# single-phase_bridge_test1.net
KiCad netlist of a schematic drawn in Altium Designer
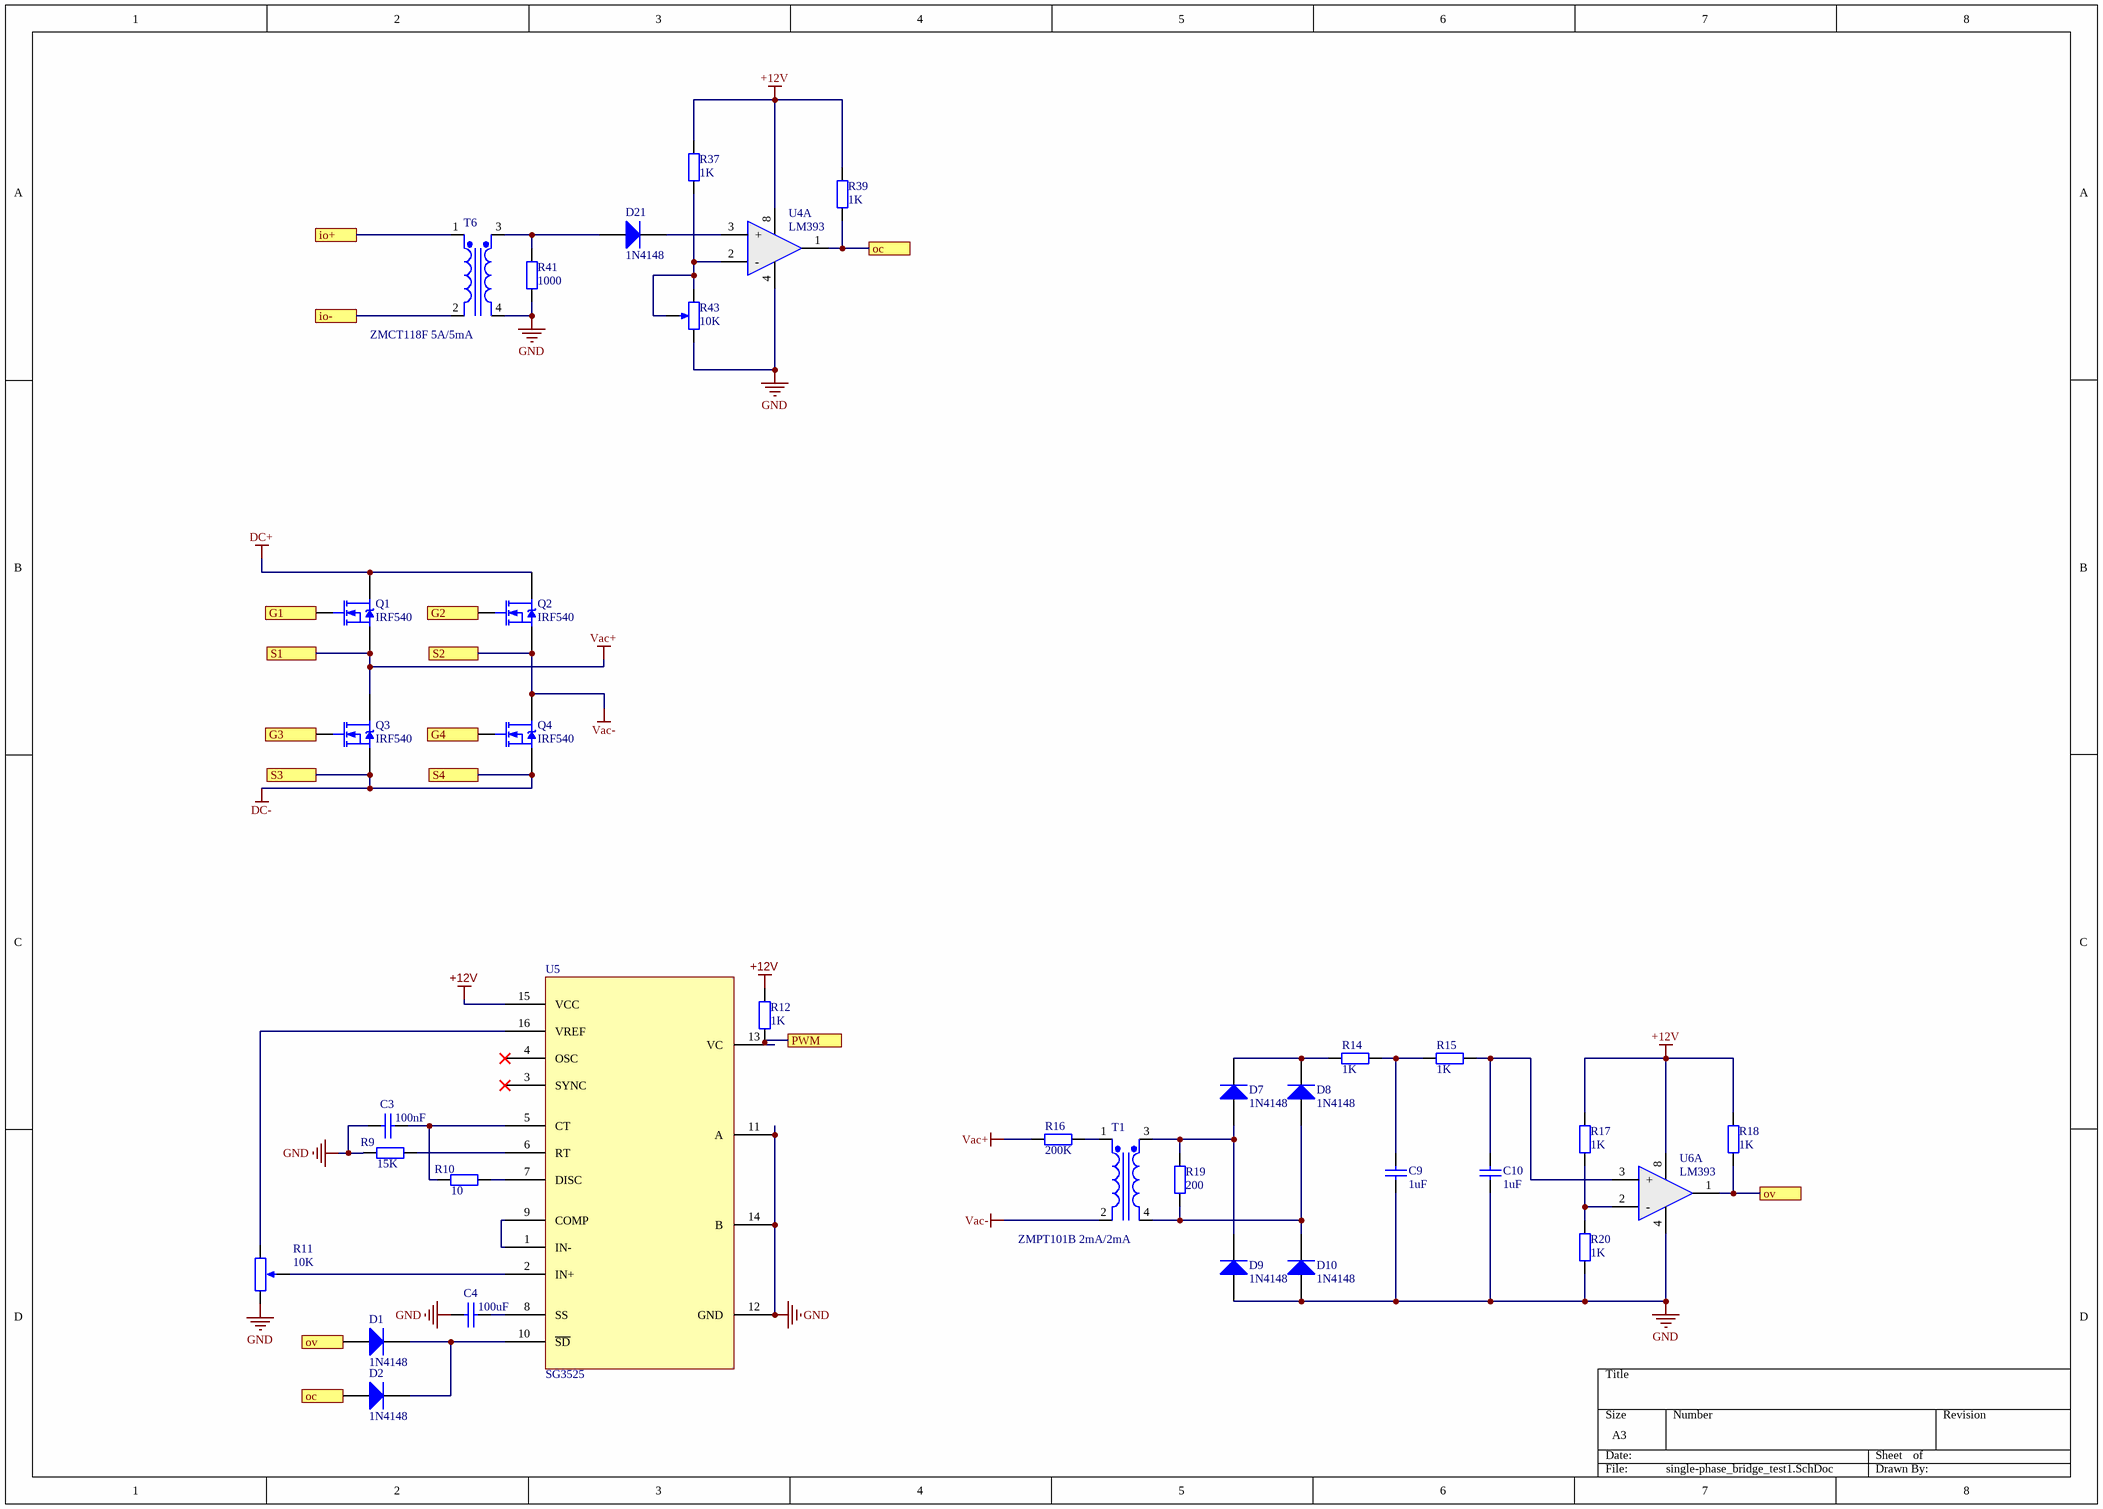
[diagram p0: single-phase_bridge_test1.SchDoc]

(export (version "E")
  (design (tool "Eeschema 10.0.6"))
  (components
    (comp (ref "C3")
      (value "100nF")
      (footprint "C0603")
      (description "Capacitor")
      (libsource (lib "XS") (part "Cap"))
    )
    (comp (ref "C4")
      (value "100uF")
      (footprint "C0603")
      (description "Capacitor")
      (libsource (lib "XS") (part "Cap"))
    )
    (comp (ref "C9")
      (value "1uF")
      (footprint "0805C")
      (description "无极性电容")
      (fields (field (name "Comment") "Cap") (field (name "PUBLISHER") "Altium Limited"))
      (libsource (lib "Capacitors") (part "Cap"))
    )
    (comp (ref "C10")
      (value "1uF")
      (footprint "0805C")
      (description "无极性电容")
      (fields (field (name "Comment") "Cap") (field (name "PUBLISHER") "Altium Limited"))
      (libsource (lib "Capacitors") (part "Cap"))
    )
    (comp (ref "D1")
      (value "Diode")
      (footprint "DIODE-SMA")
      (description "二极管")
      (fields (field (name "TYPE") "1N4148") (field (name "PUBLISHER") "Altium Limited"))
      (libsource (lib "Diodes") (part "Diode"))
    )
    (comp (ref "D2")
      (value "Diode")
      (footprint "DIODE-SMA")
      (description "二极管")
      (fields (field (name "TYPE") "1N4148") (field (name "PUBLISHER") "Altium Limited"))
      (libsource (lib "Diodes") (part "Diode"))
    )
    (comp (ref "D7")
      (value "Diode")
      (footprint "DIODE-SMA")
      (description "二极管")
      (fields (field (name "TYPE") "1N4148") (field (name "PUBLISHER") "Altium Limited"))
      (libsource (lib "Diodes") (part "Diode"))
    )
    (comp (ref "D8")
      (value "Diode")
      (footprint "DIODE-SMA")
      (description "二极管")
      (fields (field (name "TYPE") "1N4148") (field (name "PUBLISHER") "Altium Limited"))
      (libsource (lib "Diodes") (part "Diode"))
    )
    (comp (ref "D9")
      (value "Diode")
      (footprint "DIODE-SMA")
      (description "二极管")
      (fields (field (name "TYPE") "1N4148") (field (name "PUBLISHER") "Altium Limited"))
      (libsource (lib "Diodes") (part "Diode"))
    )
    (comp (ref "D10")
      (value "Diode")
      (footprint "DIODE-SMA")
      (description "二极管")
      (fields (field (name "TYPE") "1N4148") (field (name "PUBLISHER") "Altium Limited"))
      (libsource (lib "Diodes") (part "Diode"))
    )
    (comp (ref "D21")
      (value "Diode")
      (footprint "DIODE-SMA")
      (description "二极管")
      (fields (field (name "TYPE") "1N4148") (field (name "PUBLISHER") "Altium Limited"))
      (libsource (lib "Diodes") (part "Diode"))
    )
    (comp (ref "Q1")
      (value "IRF540")
      (footprint "TO-220")
      (description "N-Channel MOSFET")
      (fields (field (name "PUBLISHER") "Altium Limited"))
      (libsource (lib "Transistors") (part "MOSFET-N"))
    )
    (comp (ref "Q2")
      (value "IRF540")
      (footprint "TO-220")
      (description "N-Channel MOSFET")
      (fields (field (name "PUBLISHER") "Altium Limited"))
      (libsource (lib "Transistors") (part "MOSFET-N"))
    )
    (comp (ref "Q3")
      (value "IRF540")
      (footprint "TO-220")
      (description "N-Channel MOSFET")
      (fields (field (name "PUBLISHER") "Altium Limited"))
      (libsource (lib "Transistors") (part "MOSFET-N"))
    )
    (comp (ref "Q4")
      (value "IRF540")
      (footprint "TO-220")
      (description "N-Channel MOSFET")
      (fields (field (name "PUBLISHER") "Altium Limited"))
      (libsource (lib "Transistors") (part "MOSFET-N"))
    )
    (comp (ref "R9")
      (value "15K")
      (footprint "R0805_3D")
      (description "贴片电阻")
      (fields (field (name "Comment") "Res") (field (name "PUBLISHER") "Altium Limited"))
      (libsource (lib "XS") (part "Res"))
    )
    (comp (ref "R10")
      (value "10")
      (footprint "R0805_3D")
      (description "贴片电阻")
      (fields (field (name "Comment") "Res") (field (name "PUBLISHER") "Altium Limited"))
      (libsource (lib "XS") (part "Res"))
    )
    (comp (ref "R11")
      (value "10K")
      (footprint "RPOT")
      (description "精密可调电阻")
      (fields (field (name "Comment") "RPot") (field (name "PUBLISHER") "Altium Limited"))
      (libsource (lib "XS") (part "RPot"))
    )
    (comp (ref "R12")
      (value "1K")
      (footprint "R0805_3D")
      (description "贴片电阻")
      (fields (field (name "Comment") "Res") (field (name "PUBLISHER") "Altium Limited"))
      (libsource (lib "") (part "Res_1"))
    )
    (comp (ref "R14")
      (value "1K")
      (footprint "0805R")
      (description "Resistor")
      (fields (field (name "Comment") "Res2") (field (name "PUBLISHER") "Altium Limited"))
      (libsource (lib "") (part "Res2_1"))
    )
    (comp (ref "R15")
      (value "1K")
      (footprint "0805R")
      (description "Resistor")
      (fields (field (name "Comment") "Res2") (field (name "PUBLISHER") "Altium Limited"))
      (libsource (lib "") (part "Res2_1"))
    )
    (comp (ref "R16")
      (value "200K")
      (footprint "0805R")
      (description "Resistor")
      (fields (field (name "Comment") "Res2") (field (name "PUBLISHER") "Altium Limited"))
      (libsource (lib "") (part "Res2_2"))
    )
    (comp (ref "R17")
      (value "1K")
      (footprint "0805R")
      (description "电阻")
      (fields (field (name "PUBLISHER") "Altium Limited"))
      (libsource (lib "Resistors") (part "Res"))
    )
    (comp (ref "R18")
      (value "1K")
      (footprint "0805R")
      (description "电阻")
      (fields (field (name "PUBLISHER") "Altium Limited"))
      (libsource (lib "Resistors") (part "Res"))
    )
    (comp (ref "R19")
      (value "200")
      (footprint "0805R")
      (description "Resistor")
      (fields (field (name "Comment") "Res2") (field (name "PUBLISHER") "Altium Limited"))
      (libsource (lib "Miscellaneous Devices") (part "Res2"))
    )
    (comp (ref "R20")
      (value "1K")
      (footprint "0805R")
      (description "电阻")
      (fields (field (name "PUBLISHER") "Altium Limited"))
      (libsource (lib "Resistors") (part "Res"))
    )
    (comp (ref "R37")
      (value "1K")
      (footprint "0805R")
      (description "电阻")
      (fields (field (name "PUBLISHER") "Altium Limited"))
      (libsource (lib "Resistors") (part "Res"))
    )
    (comp (ref "R39")
      (value "1K")
      (footprint "0805R")
      (description "电阻")
      (fields (field (name "PUBLISHER") "Altium Limited"))
      (libsource (lib "Resistors") (part "Res"))
    )
    (comp (ref "R41")
      (value "1000")
      (footprint "0805R")
      (description "Resistor")
      (fields (field (name "Comment") "Res2") (field (name "PUBLISHER") "Altium Limited"))
      (libsource (lib "Miscellaneous Devices") (part "Res2"))
    )
    (comp (ref "R43")
      (value "10K")
      (footprint "RPot_3296W")
      (description "电位器")
      (fields (field (name "PUBLISHER") "Altium Limited"))
      (libsource (lib "Resistors") (part "RPot"))
    )
    (comp (ref "T1")
      (value "ZMPT101B 2mA/2mA")
      (footprint "PT ZMPT101B")
      (libsource (lib "刘爽") (part "DL-PT202H1"))
    )
    (comp (ref "T6")
      (value "ZMCT118F 5A/5mA")
      (footprint "PT ZMPT101B")
      (libsource (lib "刘爽") (part "DL-PT202H1"))
    )
    (comp (ref "U4")
      (value "LM393")
      (footprint "DIP8")
      (description "2比较器芯片")
      (libsource (lib "Amplifier") (part "LM393"))
    )
    (comp (ref "U5") (value "SG3525") (libsource (lib "XS") (part "SG3525")))
    (comp (ref "U6")
      (value "LM393")
      (footprint "DIP8")
      (description "2比较器芯片")
      (libsource (lib "Amplifier") (part "LM393"))
    )
  )
  (nets
    (net (code "1") (name "+12V") (class "Default")
      (node (ref "R12") (pin "2") (pinfunction "2_2") (pintype "passive"))
      (node (ref "R17") (pin "2") (pinfunction "2_2") (pintype "passive"))
      (node (ref "R18") (pin "2") (pinfunction "2_2") (pintype "passive"))
      (node (ref "R37") (pin "2") (pinfunction "2_2") (pintype "passive"))
      (node (ref "R39") (pin "2") (pinfunction "2_2") (pintype "passive"))
      (node (ref "U4") (pin "8") (pinfunction "V-_8") (pintype "passive"))
      (node (ref "U5") (pin "15") (pinfunction "VCC_15") (pintype "passive"))
      (node (ref "U6") (pin "8") (pinfunction "V-_8") (pintype "passive"))
    )
    (net (code "2") (name "/G1") (class "Default")
      (node (ref "Q1") (pin "1") (pinfunction "G_1") (pintype "passive"))
    )
    (net (code "3") (name "/G2") (class "Default")
      (node (ref "Q2") (pin "1") (pinfunction "G_1") (pintype "passive"))
    )
    (net (code "4") (name "/G3") (class "Default")
      (node (ref "Q3") (pin "1") (pinfunction "G_1") (pintype "passive"))
    )
    (net (code "5") (name "/G4") (class "Default")
      (node (ref "Q4") (pin "1") (pinfunction "G_1") (pintype "passive"))
    )
    (net (code "6") (name "/PWM") (class "Default")
      (node (ref "R12") (pin "1") (pinfunction "1_1") (pintype "passive"))
      (node (ref "U5") (pin "13") (pinfunction "VC_13") (pintype "passive"))
    )
    (net (code "7") (name "/io+") (class "Default")
      (node (ref "T6") (pin "1") (pinfunction "Pri+_1") (pintype "passive"))
    )
    (net (code "8") (name "/io-") (class "Default")
      (node (ref "T6") (pin "2") (pinfunction "Pri-_2") (pintype "passive"))
    )
    (net (code "9") (name "/oc") (class "Default")
      (node (ref "D2") (pin "1") (pinfunction "A_1") (pintype "passive"))
      (node (ref "R39") (pin "1") (pinfunction "1_1") (pintype "passive"))
      (node (ref "U4") (pin "1") (pinfunction "OUT_1") (pintype "passive"))
    )
    (net (code "10") (name "/ov") (class "Default")
      (node (ref "D1") (pin "1") (pinfunction "A_1") (pintype "passive"))
      (node (ref "R18") (pin "1") (pinfunction "1_1") (pintype "passive"))
      (node (ref "U6") (pin "1") (pinfunction "OUT_1") (pintype "passive"))
    )
    (net (code "11") (name "DC+") (class "Default")
      (node (ref "Q1") (pin "2") (pinfunction "D_2") (pintype "passive"))
      (node (ref "Q2") (pin "2") (pinfunction "D_2") (pintype "passive"))
    )
    (net (code "12") (name "DC-") (class "Default")
      (node (ref "Q3") (pin "3") (pinfunction "S_3") (pintype "passive"))
      (node (ref "Q4") (pin "3") (pinfunction "S_3") (pintype "passive"))
    )
    (net (code "13") (name "GND") (class "Default")
      (node (ref "C10") (pin "1") (pinfunction "1_1") (pintype "passive"))
      (node (ref "C3") (pin "1") (pinfunction "1_1") (pintype "passive"))
      (node (ref "C4") (pin "1") (pinfunction "1_1") (pintype "passive"))
      (node (ref "C9") (pin "1") (pinfunction "1_1") (pintype "passive"))
      (node (ref "D10") (pin "1") (pinfunction "A_1") (pintype "passive"))
      (node (ref "D9") (pin "1") (pinfunction "A_1") (pintype "passive"))
      (node (ref "R11") (pin "1") (pinfunction "TOP_1") (pintype "passive"))
      (node (ref "R20") (pin "1") (pinfunction "1_1") (pintype "passive"))
      (node (ref "R41") (pin "1") (pinfunction "1_1") (pintype "passive"))
      (node (ref "R43") (pin "1") (pinfunction "TOP_1") (pintype "passive"))
      (node (ref "R9") (pin "1") (pinfunction "1_1") (pintype "passive"))
      (node (ref "T6") (pin "4") (pinfunction "Sec-_4") (pintype "passive"))
      (node (ref "U4") (pin "4") (pinfunction "V+_4") (pintype "passive"))
      (node (ref "U5") (pin "11") (pinfunction "A_11") (pintype "passive"))
      (node (ref "U5") (pin "12") (pinfunction "GND_12") (pintype "passive"))
      (node (ref "U5") (pin "14") (pinfunction "B_14") (pintype "passive"))
      (node (ref "U6") (pin "4") (pinfunction "V+_4") (pintype "passive"))
    )
    (net (code "14") (name "Net-(C9-Pad2)") (class "Default")
      (node (ref "C9") (pin "2") (pinfunction "2_2") (pintype "passive"))
      (node (ref "R14") (pin "1") (pinfunction "1_1") (pintype "passive"))
      (node (ref "R15") (pin "2") (pinfunction "2_2") (pintype "passive"))
    )
    (net (code "15") (name "Net-(D1-K)") (class "Default")
      (node (ref "D1") (pin "2") (pinfunction "K_2") (pintype "passive"))
      (node (ref "D2") (pin "2") (pinfunction "K_2") (pintype "passive"))
      (node (ref "U5") (pin "10") (pinfunction "~{SD}_10") (pintype "passive"))
    )
    (net (code "16") (name "Net-(D7-A)") (class "Default")
      (node (ref "D7") (pin "1") (pinfunction "A_1") (pintype "passive"))
      (node (ref "D9") (pin "2") (pinfunction "K_2") (pintype "passive"))
      (node (ref "R19") (pin "2") (pinfunction "2_2") (pintype "passive"))
      (node (ref "T1") (pin "3") (pinfunction "Sec+_3") (pintype "passive"))
    )
    (net (code "17") (name "Net-(D7-K)") (class "Default")
      (node (ref "D7") (pin "2") (pinfunction "K_2") (pintype "passive"))
      (node (ref "D8") (pin "2") (pinfunction "K_2") (pintype "passive"))
      (node (ref "R14") (pin "2") (pinfunction "2_2") (pintype "passive"))
    )
    (net (code "18") (name "Net-(D10-K)") (class "Default")
      (node (ref "D10") (pin "2") (pinfunction "K_2") (pintype "passive"))
      (node (ref "D8") (pin "1") (pinfunction "A_1") (pintype "passive"))
      (node (ref "R19") (pin "1") (pinfunction "1_1") (pintype "passive"))
      (node (ref "T1") (pin "4") (pinfunction "Sec-_4") (pintype "passive"))
    )
    (net (code "19") (name "Net-(D21-A)") (class "Default")
      (node (ref "D21") (pin "1") (pinfunction "A_1") (pintype "passive"))
      (node (ref "R41") (pin "2") (pinfunction "2_2") (pintype "passive"))
      (node (ref "T6") (pin "3") (pinfunction "Sec+_3") (pintype "passive"))
    )
    (net (code "20") (name "Net-(D21-K)") (class "Default")
      (node (ref "D21") (pin "2") (pinfunction "K_2") (pintype "passive"))
      (node (ref "U4") (pin "3") (pinfunction "+_3") (pintype "passive"))
    )
    (net (code "21") (name "Net-(R11-BOT)") (class "Default")
      (node (ref "R11") (pin "3") (pinfunction "BOT_3") (pintype "passive"))
      (node (ref "U5") (pin "16") (pinfunction "VREF_16") (pintype "passive"))
    )
    (net (code "22") (name "Net-(R11-TAP)") (class "Default")
      (node (ref "R11") (pin "2") (pinfunction "TAP_2") (pintype "passive"))
      (node (ref "U5") (pin "2") (pinfunction "IN+_2") (pintype "passive"))
    )
    (net (code "23") (name "Net-(R43-BOT)") (class "Default")
      (node (ref "R37") (pin "1") (pinfunction "1_1") (pintype "passive"))
      (node (ref "R43") (pin "2") (pinfunction "TAP_2") (pintype "passive"))
      (node (ref "R43") (pin "3") (pinfunction "BOT_3") (pintype "passive"))
      (node (ref "U4") (pin "2") (pinfunction "-_2") (pintype "passive"))
    )
    (net (code "24") (name "Net-(T1-Pri+)") (class "Default")
      (node (ref "R16") (pin "2") (pinfunction "2_2") (pintype "passive"))
      (node (ref "T1") (pin "1") (pinfunction "Pri+_1") (pintype "passive"))
    )
    (net (code "25") (name "Net-(U5-COMP)") (class "Default")
      (node (ref "U5") (pin "1") (pinfunction "IN-_1") (pintype "passive"))
      (node (ref "U5") (pin "9") (pinfunction "COMP_9") (pintype "passive"))
    )
    (net (code "26") (name "Net-(U5-CT)") (class "Default")
      (node (ref "C3") (pin "2") (pinfunction "2_2") (pintype "passive"))
      (node (ref "R10") (pin "1") (pinfunction "1_1") (pintype "passive"))
      (node (ref "U5") (pin "5") (pinfunction "CT_5") (pintype "passive"))
    )
    (net (code "27") (name "Net-(U5-DISC)") (class "Default")
      (node (ref "R10") (pin "2") (pinfunction "2_2") (pintype "passive"))
      (node (ref "U5") (pin "7") (pinfunction "DISC_7") (pintype "passive"))
    )
    (net (code "28") (name "Net-(U5-RT)") (class "Default")
      (node (ref "R9") (pin "2") (pinfunction "2_2") (pintype "passive"))
      (node (ref "U5") (pin "6") (pinfunction "RT_6") (pintype "passive"))
    )
    (net (code "29") (name "Net-(U5-SS)") (class "Default")
      (node (ref "C4") (pin "2") (pinfunction "2_2") (pintype "passive"))
      (node (ref "U5") (pin "8") (pinfunction "SS_8") (pintype "passive"))
    )
    (net (code "30") (name "Net-(U6A-+)") (class "Default")
      (node (ref "C10") (pin "2") (pinfunction "2_2") (pintype "passive"))
      (node (ref "R15") (pin "1") (pinfunction "1_1") (pintype "passive"))
      (node (ref "U6") (pin "3") (pinfunction "+_3") (pintype "passive"))
    )
    (net (code "31") (name "Net-(U6A--)") (class "Default")
      (node (ref "R17") (pin "1") (pinfunction "1_1") (pintype "passive"))
      (node (ref "R20") (pin "2") (pinfunction "2_2") (pintype "passive"))
      (node (ref "U6") (pin "2") (pinfunction "-_2") (pintype "passive"))
    )
    (net (code "32") (name "Vac+") (class "Default")
      (node (ref "Q1") (pin "3") (pinfunction "S_3") (pintype "passive"))
      (node (ref "Q3") (pin "2") (pinfunction "D_2") (pintype "passive"))
      (node (ref "R16") (pin "1") (pinfunction "1_1") (pintype "passive"))
    )
    (net (code "33") (name "Vac-") (class "Default")
      (node (ref "Q2") (pin "3") (pinfunction "S_3") (pintype "passive"))
      (node (ref "Q4") (pin "2") (pinfunction "D_2") (pintype "passive"))
      (node (ref "T1") (pin "2") (pinfunction "Pri-_2") (pintype "passive"))
    )
    (net (code "34") (name "unconnected-(U5-OSC-Pad4)") (class "Default")
      (node (ref "U5") (pin "4") (pinfunction "OSC_4") (pintype "passive+no_connect"))
    )
    (net (code "35") (name "unconnected-(U5-SYNC-Pad3)") (class "Default")
      (node (ref "U5") (pin "3") (pinfunction "SYNC_3") (pintype "passive+no_connect"))
    )
  )
)
